# FrequencyMeter.net
KiCad netlist of a schematic drawn in Altium Designer
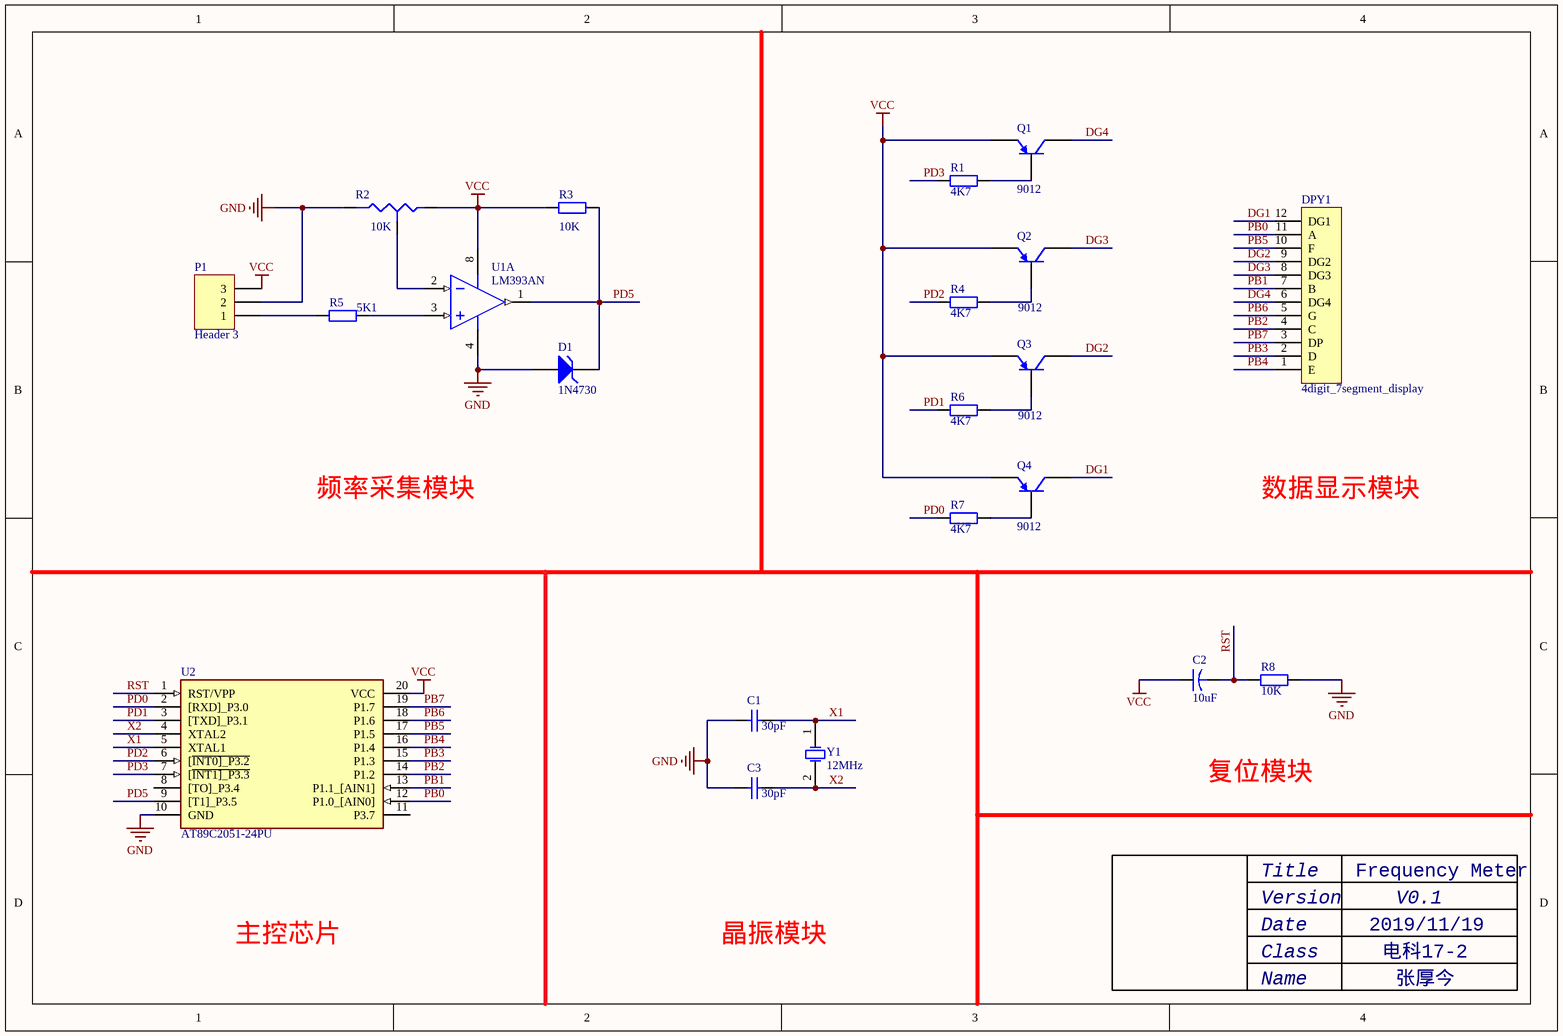
[diagram p0: FrequencyMeter.SchDoc]

(export (version "E")
  (design (tool "Eeschema 10.0.6"))
  (components
    (comp (ref "C1")
      (value "30pF")
      (footprint "RAD-0.1")
      (description "Capacitor")
      (fields (field (name "Comment") "Cap") (field (name "PUBLISHER") "Altium Limited"))
      (libsource (lib "Miscellaneous Devices") (part "Cap"))
    )
    (comp (ref "C2")
      (value "10uF")
      (footprint "CAPR5-4X5")
      (description "Capacitor")
      (fields (field (name "Comment") "Cap2") (field (name "PUBLISHER") "Altium Limited"))
      (libsource (lib "Miscellaneous Devices") (part "Cap2"))
    )
    (comp (ref "C3")
      (value "30pF")
      (footprint "RAD-0.1")
      (description "Capacitor")
      (fields (field (name "Comment") "Cap") (field (name "PUBLISHER") "Altium Limited"))
      (libsource (lib "Miscellaneous Devices") (part "Cap"))
    )
    (comp (ref "D1")
      (value "1N4730")
      (footprint "DIODE-0.4")
      (description "Zener Diode")
      (fields (field (name "PUBLISHER") "Altium Limited"))
      (libsource (lib "Miscellaneous Devices") (part "D Zener"))
    )
    (comp (ref "DPY1")
      (value "4digit_7segment_display")
      (footprint "4digit_7segment_display")
      (libsource (lib "SamacSys") (part "4digit_7segment_display"))
    )
    (comp (ref "P1")
      (value "Header 3")
      (footprint "HDR1X3")
      (description "Header, 3-Pin")
      (fields (field (name "PUBLISHER") "Altium Limited"))
      (libsource (lib "Miscellaneous Connectors") (part "Header 3"))
    )
    (comp (ref "Q1")
      (value "9012")
      (footprint "TO-226-AA")
      (description "PNP Bipolar Transistor")
      (fields (field (name "PUBLISHER") "Altium Limited"))
      (libsource (lib "Miscellaneous Devices") (part "PNP"))
    )
    (comp (ref "Q2")
      (value "9012")
      (footprint "TO-226-AA")
      (description "PNP Bipolar Transistor")
      (fields (field (name "PUBLISHER") "Altium Limited"))
      (libsource (lib "Miscellaneous Devices") (part "PNP"))
    )
    (comp (ref "Q3")
      (value "9012")
      (footprint "TO-226-AA")
      (description "PNP Bipolar Transistor")
      (fields (field (name "PUBLISHER") "Altium Limited"))
      (libsource (lib "Miscellaneous Devices") (part "PNP"))
    )
    (comp (ref "Q4")
      (value "9012")
      (footprint "TO-226-AA")
      (description "PNP Bipolar Transistor")
      (fields (field (name "PUBLISHER") "Altium Limited"))
      (libsource (lib "Miscellaneous Devices") (part "PNP"))
    )
    (comp (ref "R1")
      (value "4K7")
      (footprint "AXIAL-0.4")
      (description "Resistor")
      (fields (field (name "Comment") "Res2") (field (name "PUBLISHER") "Altium Limited"))
      (libsource (lib "") (part "Res2_1"))
    )
    (comp (ref "R2")
      (value "10K")
      (footprint "VR5")
      (description "Tapped Resistor")
      (fields (field (name "Comment") "Res Tap") (field (name "PUBLISHER") "Altium Limited"))
      (libsource (lib "Miscellaneous Devices") (part "Res Tap"))
    )
    (comp (ref "R3")
      (value "10K")
      (footprint "AXIAL-0.4")
      (description "Resistor")
      (fields (field (name "Comment") "Res2") (field (name "PUBLISHER") "Altium Limited"))
      (libsource (lib "") (part "Res2_1"))
    )
    (comp (ref "R4")
      (value "4K7")
      (footprint "AXIAL-0.4")
      (description "Resistor")
      (fields (field (name "Comment") "Res2") (field (name "PUBLISHER") "Altium Limited"))
      (libsource (lib "") (part "Res2_1"))
    )
    (comp (ref "R5")
      (value "5K1")
      (footprint "AXIAL-0.4")
      (description "Resistor")
      (fields (field (name "Comment") "Res2") (field (name "PUBLISHER") "Altium Limited"))
      (libsource (lib "") (part "Res2_1"))
    )
    (comp (ref "R6")
      (value "4K7")
      (footprint "AXIAL-0.4")
      (description "Resistor")
      (fields (field (name "Comment") "Res2") (field (name "PUBLISHER") "Altium Limited"))
      (libsource (lib "") (part "Res2_1"))
    )
    (comp (ref "R7")
      (value "4K7")
      (footprint "AXIAL-0.4")
      (description "Resistor")
      (fields (field (name "Comment") "Res2") (field (name "PUBLISHER") "Altium Limited"))
      (libsource (lib "") (part "Res2_1"))
    )
    (comp (ref "R8")
      (value "10K")
      (footprint "AXIAL-0.4")
      (description "Resistor")
      (fields (field (name "Comment") "Res2") (field (name "PUBLISHER") "Altium Limited"))
      (libsource (lib "Miscellaneous Devices") (part "Res2"))
    )
    (comp (ref "U1")
      (value "LM393AN")
      (footprint "626-05")
      (description "Dual Comparator")
      (fields (field (name "PUBLISHER") "Altium Limited"))
      (libsource (lib "Motorola Analog Comparator") (part "LM393AN"))
    )
    (comp (ref "U2")
      (value "AT89C2051-24PU")
      (footprint "SamacSys:DIP794W56P254L2591H533Q20N")
      (description "Integrated Circuit")
      (fields (field (name "MOUSER PART NUMBER") "556-A89C2051-24PU"))
      (libsource (lib "SamacSys") (part "AT89C2051-24PU"))
    )
    (comp (ref "Y1")
      (value "12MHz")
      (footprint "R38")
      (description "Crystal Oscillator")
      (fields (field (name "PUBLISHER") "Altium Limited"))
      (libsource (lib "Miscellaneous Devices") (part "XTAL"))
    )
  )
  (nets
    (net (code "1") (name "/DG1") (class "Default")
      (node (ref "DPY1") (pin "12") (pinfunction "DG1_12") (pintype "passive"))
      (node (ref "Q4") (pin "1") (pinfunction "C_1") (pintype "passive"))
    )
    (net (code "2") (name "/DG2") (class "Default")
      (node (ref "DPY1") (pin "9") (pinfunction "DG2_9") (pintype "passive"))
      (node (ref "Q3") (pin "1") (pinfunction "C_1") (pintype "passive"))
    )
    (net (code "3") (name "/DG3") (class "Default")
      (node (ref "DPY1") (pin "8") (pinfunction "DG3_8") (pintype "passive"))
      (node (ref "Q2") (pin "1") (pinfunction "C_1") (pintype "passive"))
    )
    (net (code "4") (name "/DG4") (class "Default")
      (node (ref "DPY1") (pin "6") (pinfunction "DG4_6") (pintype "passive"))
      (node (ref "Q1") (pin "1") (pinfunction "C_1") (pintype "passive"))
    )
    (net (code "5") (name "/PB0") (class "Default")
      (node (ref "DPY1") (pin "11") (pinfunction "A_11") (pintype "passive"))
      (node (ref "U2") (pin "12") (pinfunction "P1.0_[AIN0]_12") (pintype "input"))
    )
    (net (code "6") (name "/PB1") (class "Default")
      (node (ref "DPY1") (pin "7") (pinfunction "B_7") (pintype "passive"))
      (node (ref "U2") (pin "13") (pinfunction "P1.1_[AIN1]_13") (pintype "input"))
    )
    (net (code "7") (name "/PB2") (class "Default")
      (node (ref "DPY1") (pin "4") (pinfunction "C_4") (pintype "passive"))
      (node (ref "U2") (pin "14") (pinfunction "P1.2_14") (pintype "passive"))
    )
    (net (code "8") (name "/PB3") (class "Default")
      (node (ref "DPY1") (pin "2") (pinfunction "D_2") (pintype "passive"))
      (node (ref "U2") (pin "15") (pinfunction "P1.3_15") (pintype "passive"))
    )
    (net (code "9") (name "/PB4") (class "Default")
      (node (ref "DPY1") (pin "1") (pinfunction "E_1") (pintype "passive"))
      (node (ref "U2") (pin "16") (pinfunction "P1.4_16") (pintype "passive"))
    )
    (net (code "10") (name "/PB5") (class "Default")
      (node (ref "DPY1") (pin "10") (pinfunction "F_10") (pintype "passive"))
      (node (ref "U2") (pin "17") (pinfunction "P1.5_17") (pintype "passive"))
    )
    (net (code "11") (name "/PB6") (class "Default")
      (node (ref "DPY1") (pin "5") (pinfunction "G_5") (pintype "passive"))
      (node (ref "U2") (pin "18") (pinfunction "P1.6_18") (pintype "passive"))
    )
    (net (code "12") (name "/PB7") (class "Default")
      (node (ref "DPY1") (pin "3") (pinfunction "DP_3") (pintype "passive"))
      (node (ref "U2") (pin "19") (pinfunction "P1.7_19") (pintype "passive"))
    )
    (net (code "13") (name "/PD0") (class "Default")
      (node (ref "R7") (pin "1") (pinfunction "1_1") (pintype "passive"))
      (node (ref "U2") (pin "2") (pinfunction "[RXD]_P3.0_2") (pintype "passive"))
    )
    (net (code "14") (name "/PD1") (class "Default")
      (node (ref "R6") (pin "1") (pinfunction "1_1") (pintype "passive"))
      (node (ref "U2") (pin "3") (pinfunction "[TXD]_P3.1_3") (pintype "passive"))
    )
    (net (code "15") (name "/PD2") (class "Default")
      (node (ref "R4") (pin "1") (pinfunction "1_1") (pintype "passive"))
      (node (ref "U2") (pin "6") (pinfunction "[~{INT0]_P3.2}_6") (pintype "input"))
    )
    (net (code "16") (name "/PD3") (class "Default")
      (node (ref "R1") (pin "1") (pinfunction "1_1") (pintype "passive"))
      (node (ref "U2") (pin "7") (pinfunction "[~{INT1]_P3.3}_7") (pintype "input"))
    )
    (net (code "17") (name "/PD5") (class "Default")
      (node (ref "D1") (pin "2") (pinfunction "K_2") (pintype "passive"))
      (node (ref "R3") (pin "2") (pinfunction "2_2") (pintype "passive"))
      (node (ref "U1") (pin "1") (pinfunction "OUT_1") (pintype "output"))
      (node (ref "U2") (pin "9") (pinfunction "[T1]_P3.5_9") (pintype "passive"))
    )
    (net (code "18") (name "/RST") (class "Default")
      (node (ref "C2") (pin "2") (pinfunction "2_2") (pintype "passive"))
      (node (ref "R8") (pin "2") (pinfunction "2_2") (pintype "passive"))
      (node (ref "U2") (pin "1") (pinfunction "RST/VPP_1") (pintype "input"))
    )
    (net (code "19") (name "/X1") (class "Default")
      (node (ref "C1") (pin "1") (pinfunction "1_1") (pintype "passive"))
      (node (ref "U2") (pin "5") (pinfunction "XTAL1_5") (pintype "passive"))
      (node (ref "Y1") (pin "1") (pinfunction "OSC1_1") (pintype "passive"))
    )
    (net (code "20") (name "/X2") (class "Default")
      (node (ref "C3") (pin "1") (pinfunction "1_1") (pintype "passive"))
      (node (ref "U2") (pin "4") (pinfunction "XTAL2_4") (pintype "passive"))
      (node (ref "Y1") (pin "2") (pinfunction "OSC2_2") (pintype "passive"))
    )
    (net (code "21") (name "GND") (class "Default")
      (node (ref "C1") (pin "2") (pinfunction "2_2") (pintype "passive"))
      (node (ref "C3") (pin "2") (pinfunction "2_2") (pintype "passive"))
      (node (ref "D1") (pin "1") (pinfunction "A_1") (pintype "passive"))
      (node (ref "P1") (pin "2") (pinfunction "2_2") (pintype "passive"))
      (node (ref "R2") (pin "2") (pinfunction "B_2") (pintype "passive"))
      (node (ref "R8") (pin "1") (pinfunction "1_1") (pintype "passive"))
      (node (ref "U1") (pin "4") (pinfunction "GND_4") (pintype "power_in"))
      (node (ref "U2") (pin "10") (pinfunction "GND_10") (pintype "power_in"))
    )
    (net (code "22") (name "Net-(P1-Pad1)") (class "Default")
      (node (ref "P1") (pin "1") (pinfunction "1_1") (pintype "passive"))
      (node (ref "R5") (pin "1") (pinfunction "1_1") (pintype "passive"))
    )
    (net (code "23") (name "Net-(Q1-B)") (class "Default")
      (node (ref "Q1") (pin "2") (pinfunction "B_2") (pintype "passive"))
      (node (ref "R1") (pin "2") (pinfunction "2_2") (pintype "passive"))
    )
    (net (code "24") (name "Net-(Q2-B)") (class "Default")
      (node (ref "Q2") (pin "2") (pinfunction "B_2") (pintype "passive"))
      (node (ref "R4") (pin "2") (pinfunction "2_2") (pintype "passive"))
    )
    (net (code "25") (name "Net-(Q3-B)") (class "Default")
      (node (ref "Q3") (pin "2") (pinfunction "B_2") (pintype "passive"))
      (node (ref "R6") (pin "2") (pinfunction "2_2") (pintype "passive"))
    )
    (net (code "26") (name "Net-(Q4-B)") (class "Default")
      (node (ref "Q4") (pin "2") (pinfunction "B_2") (pintype "passive"))
      (node (ref "R7") (pin "2") (pinfunction "2_2") (pintype "passive"))
    )
    (net (code "27") (name "Net-(R2-TAP)") (class "Default")
      (node (ref "R2") (pin "3") (pinfunction "TAP_3") (pintype "passive"))
      (node (ref "U1") (pin "2") (pinfunction "IN-_2") (pintype "input"))
    )
    (net (code "28") (name "Net-(U1A-IN+)") (class "Default")
      (node (ref "R5") (pin "2") (pinfunction "2_2") (pintype "passive"))
      (node (ref "U1") (pin "3") (pinfunction "IN+_3") (pintype "input"))
    )
    (net (code "29") (name "VCC") (class "Default")
      (node (ref "C2") (pin "1") (pinfunction "1_1") (pintype "passive"))
      (node (ref "P1") (pin "3") (pinfunction "3_3") (pintype "passive"))
      (node (ref "Q1") (pin "3") (pinfunction "E_3") (pintype "passive"))
      (node (ref "Q2") (pin "3") (pinfunction "E_3") (pintype "passive"))
      (node (ref "Q3") (pin "3") (pinfunction "E_3") (pintype "passive"))
      (node (ref "Q4") (pin "3") (pinfunction "E_3") (pintype "passive"))
      (node (ref "R2") (pin "1") (pinfunction "A_1") (pintype "passive"))
      (node (ref "R3") (pin "1") (pinfunction "1_1") (pintype "passive"))
      (node (ref "U1") (pin "8") (pinfunction "V+_8") (pintype "power_in"))
      (node (ref "U2") (pin "20") (pinfunction "VCC_20") (pintype "power_in"))
    )
    (net (code "30") (name "unconnected-(U2-P3.7-Pad11)") (class "Default")
      (node (ref "U2") (pin "11") (pinfunction "P3.7_11") (pintype "passive"))
    )
    (net (code "31") (name "unconnected-(U2-[TO]_P3.4-Pad8)") (class "Default")
      (node (ref "U2") (pin "8") (pinfunction "[TO]_P3.4_8") (pintype "passive"))
    )
  )
)
